# copy_before_rewire.net
KiCad netlist of a schematic drawn in EAGLE
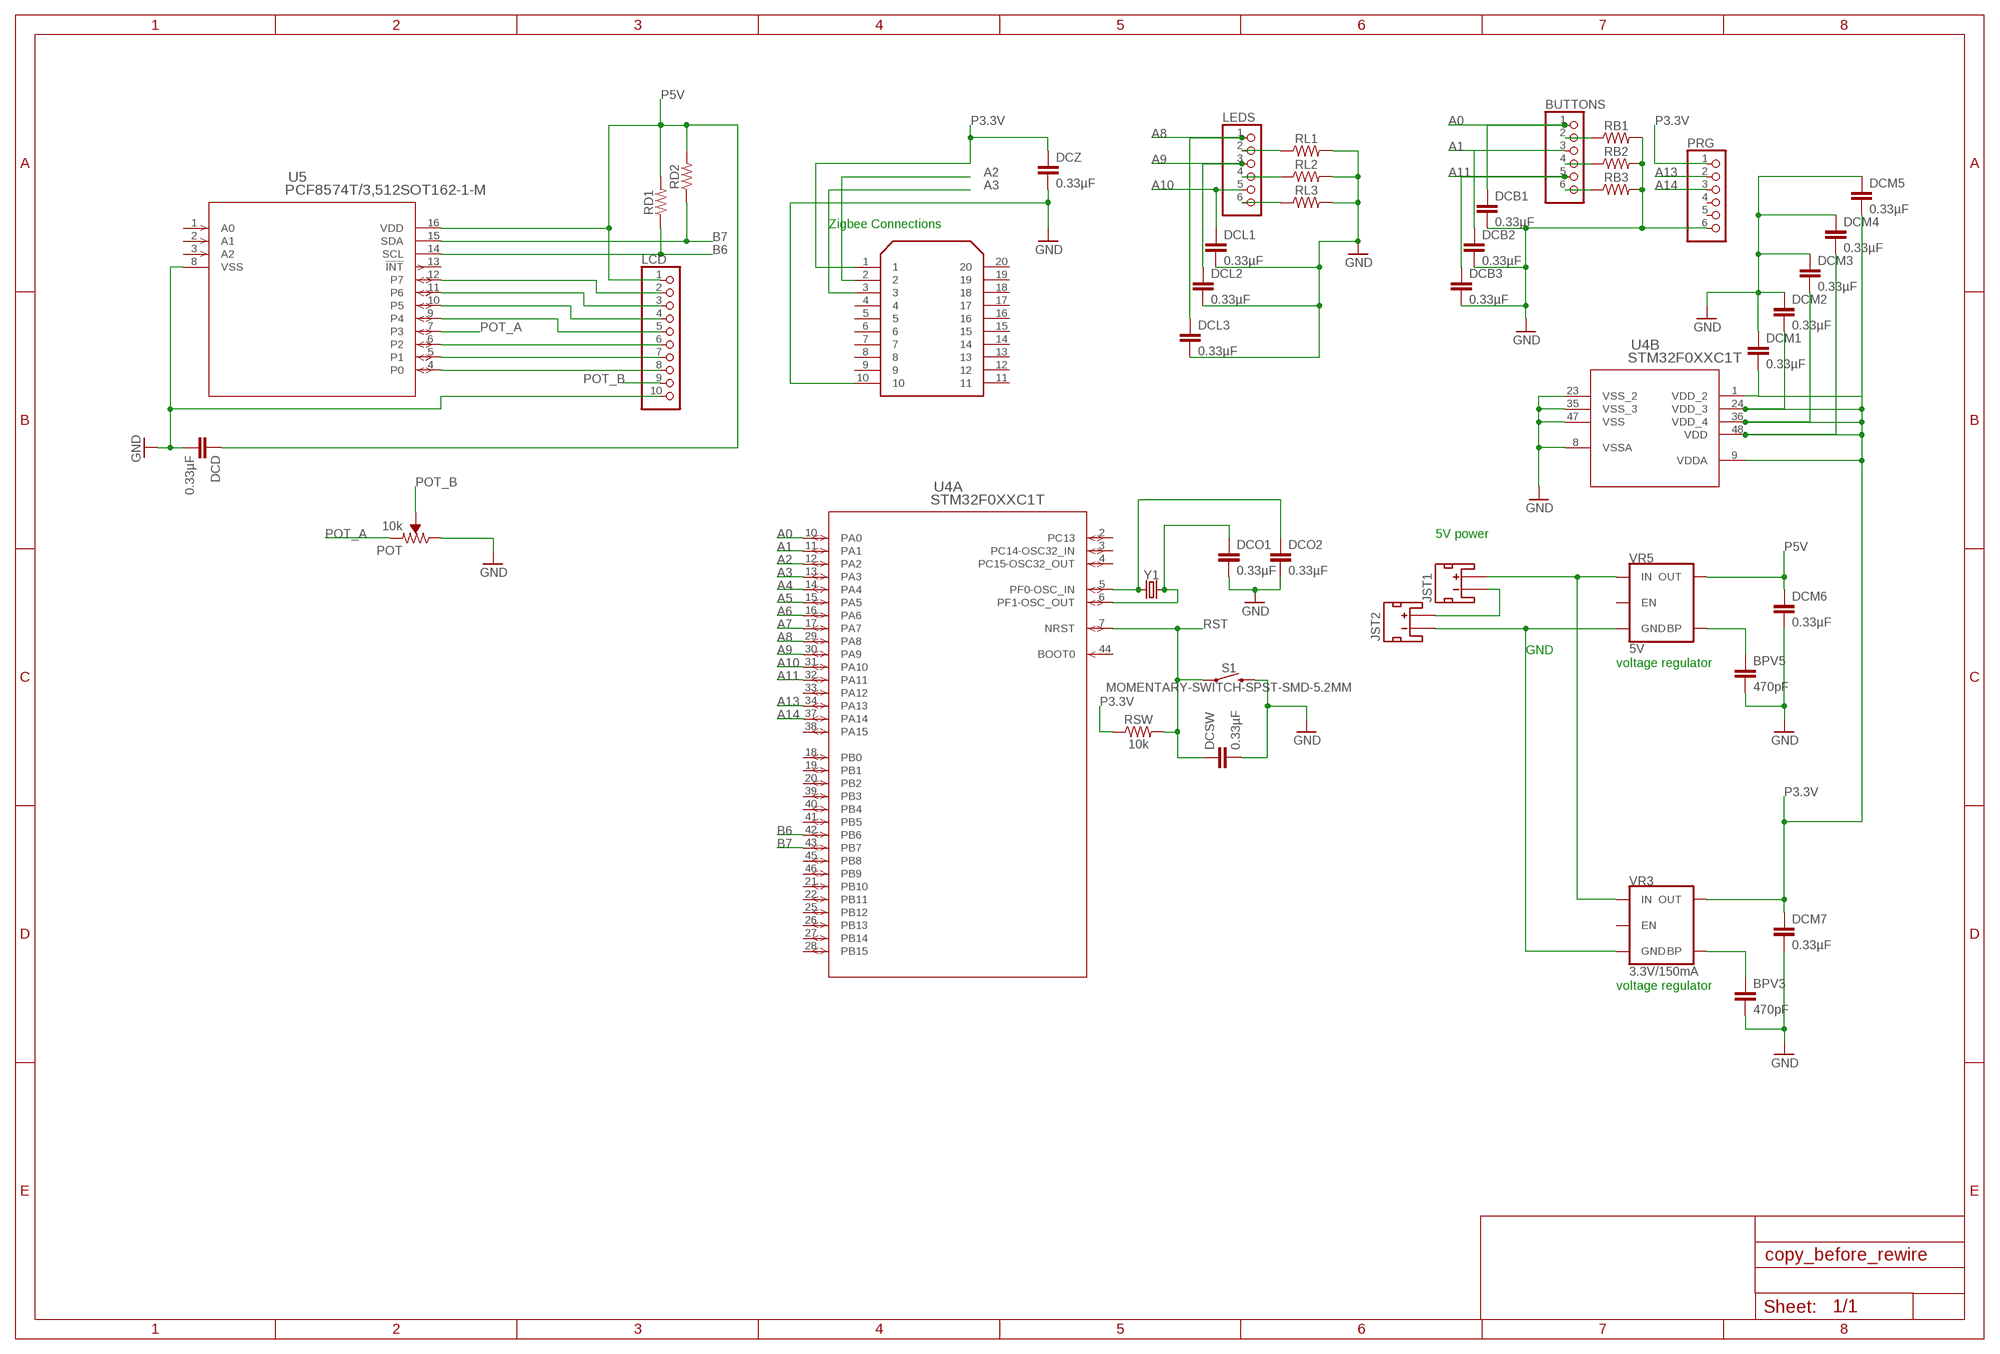
[diagram p0: schematic, sheet 1]

(export (version "E")
  (design (tool "Eeschema 10.0.6"))
  (components
    (comp (ref "BPV3")
      (value "470pF")
      (footprint "eagle-import:0603")
      (libsource (lib "eagle-import") (part "470PF-0603-50V-5%"))
    )
    (comp (ref "BPV5")
      (value "470pF")
      (footprint "eagle-import:0603")
      (libsource (lib "eagle-import") (part "470PF-0603-50V-5%"))
    )
    (comp (ref "BUTTONS")
      (value "PINHD-1X6")
      (footprint "eagle-import:1X06")
      (libsource (lib "eagle-import") (part "PINHD-1X6"))
    )
    (comp (ref "DCB1")
      (value "0.33µF")
      (footprint "eagle-import:0805")
      (libsource (lib "eagle-import") (part "0.33UF/330NF-0805-50V-10%"))
    )
    (comp (ref "DCB2")
      (value "0.33µF")
      (footprint "eagle-import:0805")
      (libsource (lib "eagle-import") (part "0.33UF/330NF-0805-50V-10%"))
    )
    (comp (ref "DCB3")
      (value "0.33µF")
      (footprint "eagle-import:0805")
      (libsource (lib "eagle-import") (part "0.33UF/330NF-0805-50V-10%"))
    )
    (comp (ref "DCD")
      (value "0.33µF")
      (footprint "eagle-import:0805")
      (libsource (lib "eagle-import") (part "0.33UF/330NF-0805-50V-10%"))
    )
    (comp (ref "DCL1")
      (value "0.33µF")
      (footprint "eagle-import:0805")
      (libsource (lib "eagle-import") (part "0.33UF/330NF-0805-50V-10%"))
    )
    (comp (ref "DCL2")
      (value "0.33µF")
      (footprint "eagle-import:0805")
      (libsource (lib "eagle-import") (part "0.33UF/330NF-0805-50V-10%"))
    )
    (comp (ref "DCL3")
      (value "0.33µF")
      (footprint "eagle-import:0805")
      (libsource (lib "eagle-import") (part "0.33UF/330NF-0805-50V-10%"))
    )
    (comp (ref "DCM1")
      (value "0.33µF")
      (footprint "eagle-import:0805")
      (libsource (lib "eagle-import") (part "0.33UF/330NF-0805-50V-10%"))
    )
    (comp (ref "DCM2")
      (value "0.33µF")
      (footprint "eagle-import:0805")
      (libsource (lib "eagle-import") (part "0.33UF/330NF-0805-50V-10%"))
    )
    (comp (ref "DCM3")
      (value "0.33µF")
      (footprint "eagle-import:0805")
      (libsource (lib "eagle-import") (part "0.33UF/330NF-0805-50V-10%"))
    )
    (comp (ref "DCM4")
      (value "0.33µF")
      (footprint "eagle-import:0805")
      (libsource (lib "eagle-import") (part "0.33UF/330NF-0805-50V-10%"))
    )
    (comp (ref "DCM5")
      (value "0.33µF")
      (footprint "eagle-import:0805")
      (libsource (lib "eagle-import") (part "0.33UF/330NF-0805-50V-10%"))
    )
    (comp (ref "DCM6")
      (value "0.33µF")
      (footprint "eagle-import:0805")
      (libsource (lib "eagle-import") (part "0.33UF/330NF-0805-50V-10%"))
    )
    (comp (ref "DCM7")
      (value "0.33µF")
      (footprint "eagle-import:0805")
      (libsource (lib "eagle-import") (part "0.33UF/330NF-0805-50V-10%"))
    )
    (comp (ref "DCO1")
      (value "0.33µF")
      (footprint "eagle-import:0805")
      (libsource (lib "eagle-import") (part "0.33UF/330NF-0805-50V-10%"))
    )
    (comp (ref "DCO2")
      (value "0.33µF")
      (footprint "eagle-import:0805")
      (libsource (lib "eagle-import") (part "0.33UF/330NF-0805-50V-10%"))
    )
    (comp (ref "DCSW")
      (value "0.33µF")
      (footprint "eagle-import:0805")
      (libsource (lib "eagle-import") (part "0.33UF/330NF-0805-50V-10%"))
    )
    (comp (ref "DCZ")
      (value "0.33µF")
      (footprint "eagle-import:0805")
      (libsource (lib "eagle-import") (part "0.33UF/330NF-0805-50V-10%"))
    )
    (comp (ref "JST1")
      (value "JST_2MM_MALE")
      (footprint "eagle-import:JST-2-SMD")
      (libsource (lib "eagle-import") (part "JST_2MM_MALE"))
    )
    (comp (ref "JST2")
      (value "JST_2MM_MALE")
      (footprint "eagle-import:JST-2-SMD")
      (libsource (lib "eagle-import") (part "JST_2MM_MALE"))
    )
    (comp (ref "LCD")
      (value "PINHD-1X10")
      (footprint "eagle-import:1X10")
      (libsource (lib "eagle-import") (part "PINHD-1X10"))
    )
    (comp (ref "LEDS")
      (value "PINHD-1X6")
      (footprint "eagle-import:1X06")
      (libsource (lib "eagle-import") (part "PINHD-1X6"))
    )
    (comp (ref "POT")
      (value "10k")
      (footprint "eagle-import:TRIMPOT-PTH-3386U")
      (libsource (lib "eagle-import") (part "TRIMPOT-PTH-10MM-KNOB-1/2W-10%"))
    )
    (comp (ref "PRG")
      (value "PINHD-1X6")
      (footprint "eagle-import:1X06")
      (libsource (lib "eagle-import") (part "PINHD-1X6"))
    )
    (comp (ref "RB1")
      (value "RESISTOR0805")
      (footprint "eagle-import:0805")
      (libsource (lib "eagle-import") (part "RESISTOR0805"))
    )
    (comp (ref "RB2")
      (value "RESISTOR0805")
      (footprint "eagle-import:0805")
      (libsource (lib "eagle-import") (part "RESISTOR0805"))
    )
    (comp (ref "RB3")
      (value "RESISTOR0805")
      (footprint "eagle-import:0805")
      (libsource (lib "eagle-import") (part "RESISTOR0805"))
    )
    (comp (ref "RD1")
      (value "RESISTOR0805")
      (footprint "eagle-import:0805")
      (libsource (lib "eagle-import") (part "RESISTOR0805"))
    )
    (comp (ref "RD2")
      (value "RESISTOR0805")
      (footprint "eagle-import:0805")
      (libsource (lib "eagle-import") (part "RESISTOR0805"))
    )
    (comp (ref "RL1")
      (value "RESISTOR0805")
      (footprint "eagle-import:0805")
      (libsource (lib "eagle-import") (part "RESISTOR0805"))
    )
    (comp (ref "RL2")
      (value "RESISTOR0805")
      (footprint "eagle-import:0805")
      (libsource (lib "eagle-import") (part "RESISTOR0805"))
    )
    (comp (ref "RL3")
      (value "RESISTOR0805")
      (footprint "eagle-import:0805")
      (libsource (lib "eagle-import") (part "RESISTOR0805"))
    )
    (comp (ref "RSW")
      (value "10k")
      (footprint "eagle-import:0603")
      (libsource (lib "eagle-import") (part "10KOHM-0603-1/10W-1%"))
    )
    (comp (ref "S1")
      (value "MOMENTARY-SWITCH-SPST-SMD-5.2MM")
      (footprint "eagle-import:TACTILE_SWITCH_SMD_5.2MM")
      (libsource (lib "eagle-import") (part "MOMENTARY-SWITCH-SPST-SMD-5.2MM"))
    )
    (comp (ref "U$1")
      (value "XB24-BPIT-004")
      (footprint "eagle-import:DIP-20")
      (fields (field (name "MF") "Digi International"))
      (libsource (lib "eagle-import") (part "XB24-BPIT-004"))
    )
    (comp (ref "U4")
      (value "STM32F0XXC1T")
      (footprint "eagle-import:LQFP48-7X7MM")
      (fields (field (name "MANUFACTURER_PART_NUMBER") "stm32f0xxc1t"))
      (libsource (lib "eagle-import") (part "STM32F0XXC1T"))
    )
    (comp (ref "U5")
      (value "PCF8574T/3,512SOT162-1-M")
      (footprint "eagle-import:SOT162-1-M")
      (fields (field (name "MANUFACTURER_PART_NUMBER") "PCF8574T3512"))
      (libsource (lib "eagle-import") (part "PCF8574T/3,512SOT162-1-M"))
    )
    (comp (ref "VR3")
      (value "3.3V/150mA")
      (footprint "eagle-import:SOT23-5")
      (libsource (lib "eagle-import") (part "V_REG_MIC52053.3V"))
    )
    (comp (ref "VR5")
      (value "5V")
      (footprint "eagle-import:SOT23-5")
      (libsource (lib "eagle-import") (part "V_REG_MIC52055V"))
    )
    (comp (ref "Y1")
      (value "CRYSTALPTH-HC49US")
      (footprint "eagle-import:HC49US")
      (libsource (lib "eagle-import") (part "CRYSTALPTH-HC49US"))
    )
  )
  (nets
    (net (code "1") (name "/A0") (class "Default")
      (node (ref "BUTTONS") (pin "1") (pinfunction "1_1") (pintype "passive"))
      (node (ref "DCB1") (pin "1") (pinfunction "1_1") (pintype "passive"))
      (node (ref "U4") (pin "10") (pinfunction "PA0_10") (pintype "bidirectional"))
    )
    (net (code "2") (name "/A1") (class "Default")
      (node (ref "BUTTONS") (pin "3") (pinfunction "3_3") (pintype "passive"))
      (node (ref "U4") (pin "11") (pinfunction "PA1_11") (pintype "bidirectional"))
    )
    (net (code "3") (name "/A2") (class "Default")
      (node (ref "U$1") (pin "2") (pinfunction "2_2") (pintype "bidirectional"))
      (node (ref "U4") (pin "12") (pinfunction "PA2_12") (pintype "bidirectional"))
    )
    (net (code "4") (name "/A3") (class "Default")
      (node (ref "U$1") (pin "3") (pinfunction "3_3") (pintype "bidirectional"))
      (node (ref "U4") (pin "13") (pinfunction "PA3_13") (pintype "bidirectional"))
    )
    (net (code "5") (name "/A4") (class "Default")
      (node (ref "U4") (pin "14") (pinfunction "PA4_14") (pintype "bidirectional"))
    )
    (net (code "6") (name "/A5") (class "Default")
      (node (ref "U4") (pin "15") (pinfunction "PA5_15") (pintype "bidirectional"))
    )
    (net (code "7") (name "/A6") (class "Default")
      (node (ref "U4") (pin "16") (pinfunction "PA6_16") (pintype "bidirectional"))
    )
    (net (code "8") (name "/A7") (class "Default")
      (node (ref "U4") (pin "17") (pinfunction "PA7_17") (pintype "bidirectional"))
    )
    (net (code "9") (name "/A8") (class "Default")
      (node (ref "DCL3") (pin "1") (pinfunction "1_1") (pintype "passive"))
      (node (ref "LEDS") (pin "1") (pinfunction "1_1") (pintype "passive"))
      (node (ref "U4") (pin "29") (pinfunction "PA8_29") (pintype "bidirectional"))
    )
    (net (code "10") (name "/A9") (class "Default")
      (node (ref "DCL2") (pin "1") (pinfunction "1_1") (pintype "passive"))
      (node (ref "LEDS") (pin "3") (pinfunction "3_3") (pintype "passive"))
      (node (ref "U4") (pin "30") (pinfunction "PA9_30") (pintype "bidirectional"))
    )
    (net (code "11") (name "/A10") (class "Default")
      (node (ref "DCL1") (pin "1") (pinfunction "1_1") (pintype "passive"))
      (node (ref "LEDS") (pin "5") (pinfunction "5_5") (pintype "passive"))
      (node (ref "U4") (pin "31") (pinfunction "PA10_31") (pintype "bidirectional"))
    )
    (net (code "12") (name "/A11") (class "Default")
      (node (ref "BUTTONS") (pin "5") (pinfunction "5_5") (pintype "passive"))
      (node (ref "DCB3") (pin "1") (pinfunction "1_1") (pintype "passive"))
      (node (ref "U4") (pin "32") (pinfunction "PA11_32") (pintype "bidirectional"))
    )
    (net (code "13") (name "/A13") (class "Default")
      (node (ref "PRG") (pin "2") (pinfunction "2_2") (pintype "passive"))
      (node (ref "U4") (pin "34") (pinfunction "PA13_34") (pintype "bidirectional"))
    )
    (net (code "14") (name "/A14") (class "Default")
      (node (ref "PRG") (pin "3") (pinfunction "3_3") (pintype "passive"))
      (node (ref "U4") (pin "37") (pinfunction "PA14_37") (pintype "bidirectional"))
    )
    (net (code "15") (name "/B6") (class "Default")
      (node (ref "RD1") (pin "1") (pinfunction "1_1") (pintype "passive"))
      (node (ref "U4") (pin "42") (pinfunction "PB6_42") (pintype "bidirectional"))
      (node (ref "U5") (pin "14") (pinfunction "SCL_14") (pintype "passive"))
    )
    (net (code "16") (name "/B7") (class "Default")
      (node (ref "RD2") (pin "1") (pinfunction "1_1") (pintype "passive"))
      (node (ref "U4") (pin "43") (pinfunction "PB7_43") (pintype "bidirectional"))
      (node (ref "U5") (pin "15") (pinfunction "SDA_15") (pintype "passive"))
    )
    (net (code "17") (name "/P3.3V") (class "Default")
      (node (ref "DCM1") (pin "2") (pinfunction "2_2") (pintype "passive"))
      (node (ref "DCM2") (pin "2") (pinfunction "2_2") (pintype "passive"))
      (node (ref "DCM3") (pin "2") (pinfunction "2_2") (pintype "passive"))
      (node (ref "DCM4") (pin "2") (pinfunction "2_2") (pintype "passive"))
      (node (ref "DCM5") (pin "2") (pinfunction "2_2") (pintype "passive"))
      (node (ref "DCM7") (pin "1") (pinfunction "1_1") (pintype "passive"))
      (node (ref "DCZ") (pin "1") (pinfunction "1_1") (pintype "passive"))
      (node (ref "PRG") (pin "1") (pinfunction "1_1") (pintype "passive"))
      (node (ref "RSW") (pin "1") (pinfunction "1_1") (pintype "passive"))
      (node (ref "U$1") (pin "1") (pinfunction "1_1") (pintype "bidirectional"))
      (node (ref "U4") (pin "1") (pinfunction "VDD_2_1") (pintype "power_in"))
      (node (ref "U4") (pin "24") (pinfunction "VDD_3_24") (pintype "power_in"))
      (node (ref "U4") (pin "36") (pinfunction "VDD_4_36") (pintype "power_in"))
      (node (ref "U4") (pin "48") (pinfunction "VDD_48") (pintype "power_in"))
      (node (ref "U4") (pin "9") (pinfunction "VDDA_9") (pintype "power_in"))
      (node (ref "VR3") (pin "5") (pinfunction "OUT_5") (pintype "passive"))
    )
    (net (code "18") (name "/P5V") (class "Default")
      (node (ref "DCD") (pin "1") (pinfunction "1_1") (pintype "passive"))
      (node (ref "DCM6") (pin "1") (pinfunction "1_1") (pintype "passive"))
      (node (ref "LCD") (pin "1") (pinfunction "1_1") (pintype "passive"))
      (node (ref "RD1") (pin "2") (pinfunction "2_2") (pintype "passive"))
      (node (ref "RD2") (pin "2") (pinfunction "2_2") (pintype "passive"))
      (node (ref "U5") (pin "16") (pinfunction "VDD_16") (pintype "power_in"))
      (node (ref "VR5") (pin "5") (pinfunction "OUT_5") (pintype "passive"))
    )
    (net (code "19") (name "/POT_A") (class "Default")
      (node (ref "POT") (pin "1") (pinfunction "CCW_1") (pintype "passive"))
      (node (ref "U5") (pin "7") (pinfunction "P3_7") (pintype "bidirectional"))
    )
    (net (code "20") (name "/POT_B") (class "Default")
      (node (ref "LCD") (pin "9") (pinfunction "9_9") (pintype "passive"))
      (node (ref "POT") (pin "2") (pinfunction "WIPER_2") (pintype "passive"))
    )
    (net (code "21") (name "/RST") (class "Default")
      (node (ref "DCSW") (pin "1") (pinfunction "1_1") (pintype "passive"))
      (node (ref "RSW") (pin "2") (pinfunction "2_2") (pintype "passive"))
      (node (ref "S1") (pin "1") (pinfunction "1_1") (pintype "passive"))
      (node (ref "U4") (pin "7") (pinfunction "NRST_7") (pintype "bidirectional"))
    )
    (net (code "22") (name "GND") (class "Default")
      (node (ref "BPV3") (pin "2") (pinfunction "2_2") (pintype "passive"))
      (node (ref "BPV5") (pin "2") (pinfunction "2_2") (pintype "passive"))
      (node (ref "DCB1") (pin "2") (pinfunction "2_2") (pintype "passive"))
      (node (ref "DCB2") (pin "2") (pinfunction "2_2") (pintype "passive"))
      (node (ref "DCB3") (pin "2") (pinfunction "2_2") (pintype "passive"))
      (node (ref "DCD") (pin "2") (pinfunction "2_2") (pintype "passive"))
      (node (ref "DCL1") (pin "2") (pinfunction "2_2") (pintype "passive"))
      (node (ref "DCL2") (pin "2") (pinfunction "2_2") (pintype "passive"))
      (node (ref "DCL3") (pin "2") (pinfunction "2_2") (pintype "passive"))
      (node (ref "DCM1") (pin "1") (pinfunction "1_1") (pintype "passive"))
      (node (ref "DCM2") (pin "1") (pinfunction "1_1") (pintype "passive"))
      (node (ref "DCM3") (pin "1") (pinfunction "1_1") (pintype "passive"))
      (node (ref "DCM4") (pin "1") (pinfunction "1_1") (pintype "passive"))
      (node (ref "DCM5") (pin "1") (pinfunction "1_1") (pintype "passive"))
      (node (ref "DCM6") (pin "2") (pinfunction "2_2") (pintype "passive"))
      (node (ref "DCM7") (pin "2") (pinfunction "2_2") (pintype "passive"))
      (node (ref "DCO1") (pin "2") (pinfunction "2_2") (pintype "passive"))
      (node (ref "DCO2") (pin "2") (pinfunction "2_2") (pintype "passive"))
      (node (ref "DCSW") (pin "2") (pinfunction "2_2") (pintype "passive"))
      (node (ref "DCZ") (pin "2") (pinfunction "2_2") (pintype "passive"))
      (node (ref "LCD") (pin "10") (pinfunction "10_10") (pintype "passive"))
      (node (ref "POT") (pin "3") (pinfunction "CW_3") (pintype "passive"))
      (node (ref "PRG") (pin "6") (pinfunction "6_6") (pintype "passive"))
      (node (ref "RB1") (pin "2") (pinfunction "2_2") (pintype "passive"))
      (node (ref "RB2") (pin "2") (pinfunction "2_2") (pintype "passive"))
      (node (ref "RB3") (pin "2") (pinfunction "2_2") (pintype "passive"))
      (node (ref "RL1") (pin "2") (pinfunction "2_2") (pintype "passive"))
      (node (ref "RL2") (pin "2") (pinfunction "2_2") (pintype "passive"))
      (node (ref "RL3") (pin "2") (pinfunction "2_2") (pintype "passive"))
      (node (ref "S1") (pin "3") (pinfunction "2_3") (pintype "passive"))
      (node (ref "U$1") (pin "10") (pinfunction "10_10") (pintype "bidirectional"))
      (node (ref "U4") (pin "23") (pinfunction "VSS_2_23") (pintype "power_in"))
      (node (ref "U4") (pin "35") (pinfunction "VSS_3_35") (pintype "power_in"))
      (node (ref "U4") (pin "47") (pinfunction "VSS_47") (pintype "power_in"))
      (node (ref "U4") (pin "8") (pinfunction "VSSA_8") (pintype "power_in"))
      (node (ref "U5") (pin "8") (pinfunction "VSS_8") (pintype "power_in"))
    )
    (net (code "23") (name "Net-(BUTTONS-Pad2)") (class "Default")
      (node (ref "BUTTONS") (pin "2") (pinfunction "2_2") (pintype "passive"))
      (node (ref "RB1") (pin "1") (pinfunction "1_1") (pintype "passive"))
    )
    (net (code "24") (name "Net-(BUTTONS-Pad4)") (class "Default")
      (node (ref "BUTTONS") (pin "4") (pinfunction "4_4") (pintype "passive"))
      (node (ref "RB2") (pin "1") (pinfunction "1_1") (pintype "passive"))
    )
    (net (code "25") (name "Net-(BUTTONS-Pad6)") (class "Default")
      (node (ref "BUTTONS") (pin "6") (pinfunction "6_6") (pintype "passive"))
      (node (ref "RB3") (pin "1") (pinfunction "1_1") (pintype "passive"))
    )
    (net (code "26") (name "Net-(JST1-+)") (class "Default")
      (node (ref "JST1") (pin "2") (pinfunction "+_2") (pintype "bidirectional"))
      (node (ref "VR3") (pin "1") (pinfunction "IN_1") (pintype "input"))
      (node (ref "VR5") (pin "1") (pinfunction "IN_1") (pintype "input"))
    )
    (net (code "27") (name "Net-(JST1--)") (class "Default")
      (node (ref "JST1") (pin "1") (pinfunction "-_1") (pintype "bidirectional"))
      (node (ref "JST2") (pin "2") (pinfunction "+_2") (pintype "bidirectional"))
    )
    (net (code "28") (name "Net-(JST2--)") (class "Default")
      (node (ref "JST2") (pin "1") (pinfunction "-_1") (pintype "bidirectional"))
      (node (ref "VR3") (pin "2") (pinfunction "GND_2") (pintype "input"))
      (node (ref "VR5") (pin "2") (pinfunction "GND_2") (pintype "input"))
    )
    (net (code "29") (name "Net-(LEDS-Pad2)") (class "Default")
      (node (ref "LEDS") (pin "2") (pinfunction "2_2") (pintype "passive"))
      (node (ref "RL1") (pin "1") (pinfunction "1_1") (pintype "passive"))
    )
    (net (code "30") (name "Net-(LEDS-Pad4)") (class "Default")
      (node (ref "LEDS") (pin "4") (pinfunction "4_4") (pintype "passive"))
      (node (ref "RL2") (pin "1") (pinfunction "1_1") (pintype "passive"))
    )
    (net (code "31") (name "Net-(LEDS-Pad6)") (class "Default")
      (node (ref "LEDS") (pin "6") (pinfunction "6_6") (pintype "passive"))
      (node (ref "RL3") (pin "1") (pinfunction "1_1") (pintype "passive"))
    )
    (net (code "32") (name "Net-(U4A-PF0-OSC_IN)") (class "Default")
      (node (ref "DCO2") (pin "1") (pinfunction "1_1") (pintype "passive"))
      (node (ref "U4") (pin "5") (pinfunction "PF0-OSC_IN_5") (pintype "bidirectional"))
      (node (ref "Y1") (pin "1") (pinfunction "1_1") (pintype "passive"))
    )
    (net (code "33") (name "Net-(U4A-PF1-OSC_OUT)") (class "Default")
      (node (ref "DCO1") (pin "1") (pinfunction "1_1") (pintype "passive"))
      (node (ref "U4") (pin "6") (pinfunction "PF1-OSC_OUT_6") (pintype "bidirectional"))
      (node (ref "Y1") (pin "2") (pinfunction "2_2") (pintype "passive"))
    )
    (net (code "34") (name "Net-(U5-P0)") (class "Default")
      (node (ref "LCD") (pin "8") (pinfunction "8_8") (pintype "passive"))
      (node (ref "U5") (pin "4") (pinfunction "P0_4") (pintype "bidirectional"))
    )
    (net (code "35") (name "Net-(U5-P1)") (class "Default")
      (node (ref "LCD") (pin "7") (pinfunction "7_7") (pintype "passive"))
      (node (ref "U5") (pin "5") (pinfunction "P1_5") (pintype "bidirectional"))
    )
    (net (code "36") (name "Net-(U5-P2)") (class "Default")
      (node (ref "LCD") (pin "6") (pinfunction "6_6") (pintype "passive"))
      (node (ref "U5") (pin "6") (pinfunction "P2_6") (pintype "bidirectional"))
    )
    (net (code "37") (name "Net-(U5-P4)") (class "Default")
      (node (ref "LCD") (pin "5") (pinfunction "5_5") (pintype "passive"))
      (node (ref "U5") (pin "9") (pinfunction "P4_9") (pintype "bidirectional"))
    )
    (net (code "38") (name "Net-(U5-P5)") (class "Default")
      (node (ref "LCD") (pin "4") (pinfunction "4_4") (pintype "passive"))
      (node (ref "U5") (pin "10") (pinfunction "P5_10") (pintype "bidirectional"))
    )
    (net (code "39") (name "Net-(U5-P6)") (class "Default")
      (node (ref "LCD") (pin "3") (pinfunction "3_3") (pintype "passive"))
      (node (ref "U5") (pin "11") (pinfunction "P6_11") (pintype "bidirectional"))
    )
    (net (code "40") (name "Net-(U5-P7)") (class "Default")
      (node (ref "LCD") (pin "2") (pinfunction "2_2") (pintype "passive"))
      (node (ref "U5") (pin "12") (pinfunction "P7_12") (pintype "bidirectional"))
    )
    (net (code "41") (name "Net-(VR3-BP)") (class "Default")
      (node (ref "BPV3") (pin "1") (pinfunction "1_1") (pintype "passive"))
      (node (ref "VR3") (pin "4") (pinfunction "BP_4") (pintype "input"))
    )
    (net (code "42") (name "Net-(VR5-BP)") (class "Default")
      (node (ref "BPV5") (pin "1") (pinfunction "1_1") (pintype "passive"))
      (node (ref "VR5") (pin "4") (pinfunction "BP_4") (pintype "input"))
    )
    (net (code "43") (name "unconnected-(DCB2-Pad1)") (class "Default")
      (node (ref "DCB2") (pin "1") (pinfunction "1_1") (pintype "passive"))
    )
    (net (code "44") (name "unconnected-(JST1-PAD1-PadNC1)") (class "Default")
      (node (ref "JST1") (pin "NC1") (pinfunction "PAD1_NC1") (pintype "bidirectional"))
    )
    (net (code "45") (name "unconnected-(JST1-PAD2-PadNC2)") (class "Default")
      (node (ref "JST1") (pin "NC2") (pinfunction "PAD2_NC2") (pintype "bidirectional"))
    )
    (net (code "46") (name "unconnected-(JST2-PAD1-PadNC1)") (class "Default")
      (node (ref "JST2") (pin "NC1") (pinfunction "PAD1_NC1") (pintype "bidirectional"))
    )
    (net (code "47") (name "unconnected-(JST2-PAD2-PadNC2)") (class "Default")
      (node (ref "JST2") (pin "NC2") (pinfunction "PAD2_NC2") (pintype "bidirectional"))
    )
    (net (code "48") (name "unconnected-(PRG-Pad4)") (class "Default")
      (node (ref "PRG") (pin "4") (pinfunction "4_4") (pintype "passive"))
    )
    (net (code "49") (name "unconnected-(PRG-Pad5)") (class "Default")
      (node (ref "PRG") (pin "5") (pinfunction "5_5") (pintype "passive"))
    )
    (net (code "50") (name "unconnected-(U$1-Pad4)") (class "Default")
      (node (ref "U$1") (pin "4") (pinfunction "4_4") (pintype "bidirectional"))
    )
    (net (code "51") (name "unconnected-(U$1-Pad5)") (class "Default")
      (node (ref "U$1") (pin "5") (pinfunction "5_5") (pintype "bidirectional"))
    )
    (net (code "52") (name "unconnected-(U$1-Pad6)") (class "Default")
      (node (ref "U$1") (pin "6") (pinfunction "6_6") (pintype "bidirectional"))
    )
    (net (code "53") (name "unconnected-(U$1-Pad7)") (class "Default")
      (node (ref "U$1") (pin "7") (pinfunction "7_7") (pintype "bidirectional"))
    )
    (net (code "54") (name "unconnected-(U$1-Pad8)") (class "Default")
      (node (ref "U$1") (pin "8") (pinfunction "8_8") (pintype "bidirectional"))
    )
    (net (code "55") (name "unconnected-(U$1-Pad9)") (class "Default")
      (node (ref "U$1") (pin "9") (pinfunction "9_9") (pintype "bidirectional"))
    )
    (net (code "56") (name "unconnected-(U$1-Pad11)") (class "Default")
      (node (ref "U$1") (pin "11") (pinfunction "11_11") (pintype "bidirectional"))
    )
    (net (code "57") (name "unconnected-(U$1-Pad12)") (class "Default")
      (node (ref "U$1") (pin "12") (pinfunction "12_12") (pintype "bidirectional"))
    )
    (net (code "58") (name "unconnected-(U$1-Pad13)") (class "Default")
      (node (ref "U$1") (pin "13") (pinfunction "13_13") (pintype "bidirectional"))
    )
    (net (code "59") (name "unconnected-(U$1-Pad14)") (class "Default")
      (node (ref "U$1") (pin "14") (pinfunction "14_14") (pintype "bidirectional"))
    )
    (net (code "60") (name "unconnected-(U$1-Pad15)") (class "Default")
      (node (ref "U$1") (pin "15") (pinfunction "15_15") (pintype "bidirectional"))
    )
    (net (code "61") (name "unconnected-(U$1-Pad16)") (class "Default")
      (node (ref "U$1") (pin "16") (pinfunction "16_16") (pintype "bidirectional"))
    )
    (net (code "62") (name "unconnected-(U$1-Pad17)") (class "Default")
      (node (ref "U$1") (pin "17") (pinfunction "17_17") (pintype "bidirectional"))
    )
    (net (code "63") (name "unconnected-(U$1-Pad18)") (class "Default")
      (node (ref "U$1") (pin "18") (pinfunction "18_18") (pintype "bidirectional"))
    )
    (net (code "64") (name "unconnected-(U$1-Pad19)") (class "Default")
      (node (ref "U$1") (pin "19") (pinfunction "19_19") (pintype "bidirectional"))
    )
    (net (code "65") (name "unconnected-(U$1-Pad20)") (class "Default")
      (node (ref "U$1") (pin "20") (pinfunction "20_20") (pintype "bidirectional"))
    )
    (net (code "66") (name "unconnected-(U4A-BOOT0-Pad44)") (class "Default")
      (node (ref "U4") (pin "44") (pinfunction "BOOT0_44") (pintype "input"))
    )
    (net (code "67") (name "unconnected-(U4A-PA12-Pad33)") (class "Default")
      (node (ref "U4") (pin "33") (pinfunction "PA12_33") (pintype "bidirectional"))
    )
    (net (code "68") (name "unconnected-(U4A-PA15-Pad38)") (class "Default")
      (node (ref "U4") (pin "38") (pinfunction "PA15_38") (pintype "bidirectional"))
    )
    (net (code "69") (name "unconnected-(U4A-PB0-Pad18)") (class "Default")
      (node (ref "U4") (pin "18") (pinfunction "PB0_18") (pintype "bidirectional"))
    )
    (net (code "70") (name "unconnected-(U4A-PB1-Pad19)") (class "Default")
      (node (ref "U4") (pin "19") (pinfunction "PB1_19") (pintype "bidirectional"))
    )
    (net (code "71") (name "unconnected-(U4A-PB2-Pad20)") (class "Default")
      (node (ref "U4") (pin "20") (pinfunction "PB2_20") (pintype "bidirectional"))
    )
    (net (code "72") (name "unconnected-(U4A-PB3-Pad39)") (class "Default")
      (node (ref "U4") (pin "39") (pinfunction "PB3_39") (pintype "bidirectional"))
    )
    (net (code "73") (name "unconnected-(U4A-PB4-Pad40)") (class "Default")
      (node (ref "U4") (pin "40") (pinfunction "PB4_40") (pintype "bidirectional"))
    )
    (net (code "74") (name "unconnected-(U4A-PB5-Pad41)") (class "Default")
      (node (ref "U4") (pin "41") (pinfunction "PB5_41") (pintype "bidirectional"))
    )
    (net (code "75") (name "unconnected-(U4A-PB8-Pad45)") (class "Default")
      (node (ref "U4") (pin "45") (pinfunction "PB8_45") (pintype "bidirectional"))
    )
    (net (code "76") (name "unconnected-(U4A-PB9-Pad46)") (class "Default")
      (node (ref "U4") (pin "46") (pinfunction "PB9_46") (pintype "bidirectional"))
    )
    (net (code "77") (name "unconnected-(U4A-PB10-Pad21)") (class "Default")
      (node (ref "U4") (pin "21") (pinfunction "PB10_21") (pintype "bidirectional"))
    )
    (net (code "78") (name "unconnected-(U4A-PB11-Pad22)") (class "Default")
      (node (ref "U4") (pin "22") (pinfunction "PB11_22") (pintype "bidirectional"))
    )
    (net (code "79") (name "unconnected-(U4A-PB12-Pad25)") (class "Default")
      (node (ref "U4") (pin "25") (pinfunction "PB12_25") (pintype "bidirectional"))
    )
    (net (code "80") (name "unconnected-(U4A-PB13-Pad26)") (class "Default")
      (node (ref "U4") (pin "26") (pinfunction "PB13_26") (pintype "bidirectional"))
    )
    (net (code "81") (name "unconnected-(U4A-PB14-Pad27)") (class "Default")
      (node (ref "U4") (pin "27") (pinfunction "PB14_27") (pintype "bidirectional"))
    )
    (net (code "82") (name "unconnected-(U4A-PB15-Pad28)") (class "Default")
      (node (ref "U4") (pin "28") (pinfunction "PB15_28") (pintype "bidirectional"))
    )
    (net (code "83") (name "unconnected-(U4A-PC13-Pad2)") (class "Default")
      (node (ref "U4") (pin "2") (pinfunction "PC13_2") (pintype "bidirectional"))
    )
    (net (code "84") (name "unconnected-(U4A-PC14-OSC32_IN-Pad3)") (class "Default")
      (node (ref "U4") (pin "3") (pinfunction "PC14-OSC32_IN_3") (pintype "bidirectional"))
    )
    (net (code "85") (name "unconnected-(U4A-PC15-OSC32_OUT-Pad4)") (class "Default")
      (node (ref "U4") (pin "4") (pinfunction "PC15-OSC32_OUT_4") (pintype "bidirectional"))
    )
    (net (code "86") (name "unconnected-(U5-A0-Pad1)") (class "Default")
      (node (ref "U5") (pin "1") (pinfunction "A0_1") (pintype "input"))
    )
    (net (code "87") (name "unconnected-(U5-A1-Pad2)") (class "Default")
      (node (ref "U5") (pin "2") (pinfunction "A1_2") (pintype "input"))
    )
    (net (code "88") (name "unconnected-(U5-A2-Pad3)") (class "Default")
      (node (ref "U5") (pin "3") (pinfunction "A2_3") (pintype "input"))
    )
    (net (code "89") (name "unconnected-(U5-~{INT}-Pad13)") (class "Default")
      (node (ref "U5") (pin "13") (pinfunction "~{INT}_13") (pintype "output"))
    )
    (net (code "90") (name "unconnected-(VR3-EN-Pad3)") (class "Default")
      (node (ref "VR3") (pin "3") (pinfunction "EN_3") (pintype "input"))
    )
    (net (code "91") (name "unconnected-(VR5-EN-Pad3)") (class "Default")
      (node (ref "VR5") (pin "3") (pinfunction "EN_3") (pintype "input"))
    )
  )
)
